# RELAY.net
KiCad netlist of a schematic drawn in Altium Designer
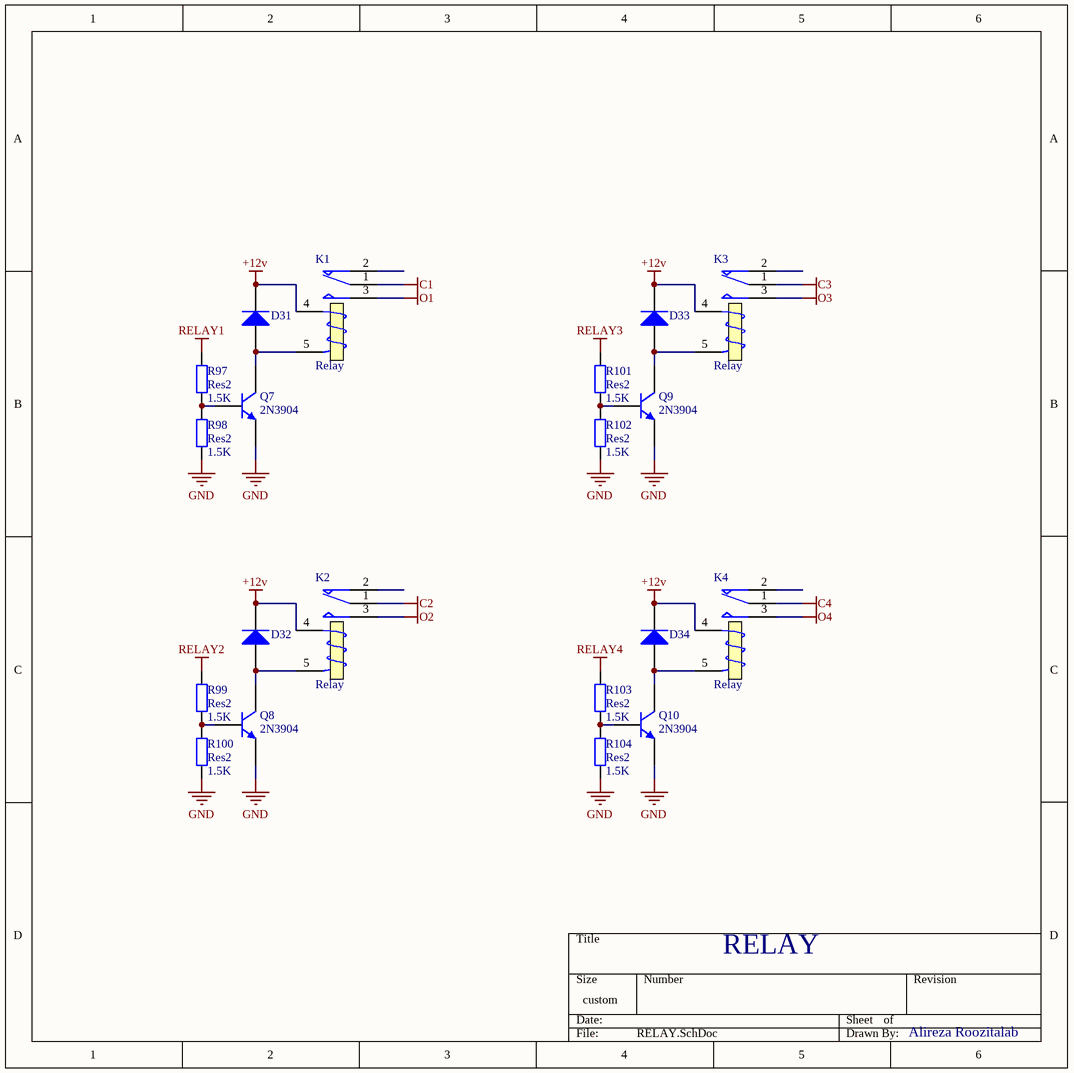
[diagram p0: RELAY.SchDoc]

(export (version "E")
  (design (tool "Eeschema 10.0.6"))
  (components
    (comp (ref "D31")
      (value "Diode 1N4148")
      (footprint "Diode-1n4148 - SMD PAD")
      (description "High Conductance Fast Diode")
      (fields (field (name "PUBLISHER") "Altium Limited"))
      (libsource (lib "Miscellaneous Devices") (part "Diode 1N4148"))
    )
    (comp (ref "D32")
      (value "Diode 1N4148")
      (footprint "Diode-1n4148 - SMD PAD")
      (description "High Conductance Fast Diode")
      (fields (field (name "PUBLISHER") "Altium Limited"))
      (libsource (lib "Miscellaneous Devices") (part "Diode 1N4148"))
    )
    (comp (ref "D33")
      (value "Diode 1N4148")
      (footprint "Diode-1n4148 - SMD PAD")
      (description "High Conductance Fast Diode")
      (fields (field (name "PUBLISHER") "Altium Limited"))
      (libsource (lib "Miscellaneous Devices") (part "Diode 1N4148"))
    )
    (comp (ref "D34")
      (value "Diode 1N4148")
      (footprint "Diode-1n4148 - SMD PAD")
      (description "High Conductance Fast Diode")
      (fields (field (name "PUBLISHER") "Altium Limited"))
      (libsource (lib "Miscellaneous Devices") (part "Diode 1N4148"))
    )
    (comp (ref "K1")
      (value "Relay")
      (footprint "RELAY 12V ATX203")
      (description "SPDT Relay")
      (fields (field (name "PUBLISHER") "Altium Limited"))
      (libsource (lib "Miscellaneous Devices") (part "Relay"))
    )
    (comp (ref "K2")
      (value "Relay")
      (footprint "RELAY 12V ATX203")
      (description "SPDT Relay")
      (fields (field (name "PUBLISHER") "Altium Limited"))
      (libsource (lib "Miscellaneous Devices") (part "Relay"))
    )
    (comp (ref "K3")
      (value "Relay")
      (footprint "RELAY 12V ATX203")
      (description "SPDT Relay")
      (fields (field (name "PUBLISHER") "Altium Limited"))
      (libsource (lib "Miscellaneous Devices") (part "Relay"))
    )
    (comp (ref "K4")
      (value "Relay")
      (footprint "RELAY 12V ATX203")
      (description "SPDT Relay")
      (fields (field (name "PUBLISHER") "Altium Limited"))
      (libsource (lib "Miscellaneous Devices") (part "Relay"))
    )
    (comp (ref "Q7")
      (value "2N3904")
      (footprint "2N3906_SMD")
      (description "NPN General Purpose Amplifier")
      (fields (field (name "PUBLISHER") "Altium Limited"))
      (libsource (lib "Miscellaneous Devices") (part "2N3904"))
    )
    (comp (ref "Q8")
      (value "2N3904")
      (footprint "2N3906_SMD")
      (description "NPN General Purpose Amplifier")
      (fields (field (name "PUBLISHER") "Altium Limited"))
      (libsource (lib "Miscellaneous Devices") (part "2N3904"))
    )
    (comp (ref "Q9")
      (value "2N3904")
      (footprint "2N3906_SMD")
      (description "NPN General Purpose Amplifier")
      (fields (field (name "PUBLISHER") "Altium Limited"))
      (libsource (lib "Miscellaneous Devices") (part "2N3904"))
    )
    (comp (ref "Q10")
      (value "2N3904")
      (footprint "2N3906_SMD")
      (description "NPN General Purpose Amplifier")
      (fields (field (name "PUBLISHER") "Altium Limited"))
      (libsource (lib "Miscellaneous Devices") (part "2N3904"))
    )
    (comp (ref "R97")
      (value "Res2")
      (footprint "RES 1206 (3216X08L)")
      (description "Resistor")
      (fields (field (name "ALTIUM_VALUE") "1.5K") (field (name "PUBLISHER") "Altium Limited"))
      (libsource (lib "Miscellaneous Devices") (part "Res2"))
    )
    (comp (ref "R98")
      (value "Res2")
      (footprint "RES 1206 (3216X08L)")
      (description "Resistor")
      (fields (field (name "ALTIUM_VALUE") "1.5K") (field (name "PUBLISHER") "Altium Limited"))
      (libsource (lib "Miscellaneous Devices") (part "Res2"))
    )
    (comp (ref "R99")
      (value "Res2")
      (footprint "RES 1206 (3216X08L)")
      (description "Resistor")
      (fields (field (name "ALTIUM_VALUE") "1.5K") (field (name "PUBLISHER") "Altium Limited"))
      (libsource (lib "Miscellaneous Devices") (part "Res2"))
    )
    (comp (ref "R100")
      (value "Res2")
      (footprint "RES 1206 (3216X08L)")
      (description "Resistor")
      (fields (field (name "ALTIUM_VALUE") "1.5K") (field (name "PUBLISHER") "Altium Limited"))
      (libsource (lib "Miscellaneous Devices") (part "Res2"))
    )
    (comp (ref "R101")
      (value "Res2")
      (footprint "RES 1206 (3216X08L)")
      (description "Resistor")
      (fields (field (name "ALTIUM_VALUE") "1.5K") (field (name "PUBLISHER") "Altium Limited"))
      (libsource (lib "Miscellaneous Devices") (part "Res2"))
    )
    (comp (ref "R102")
      (value "Res2")
      (footprint "RES 1206 (3216X08L)")
      (description "Resistor")
      (fields (field (name "ALTIUM_VALUE") "1.5K") (field (name "PUBLISHER") "Altium Limited"))
      (libsource (lib "Miscellaneous Devices") (part "Res2"))
    )
    (comp (ref "R103")
      (value "Res2")
      (footprint "RES 1206 (3216X08L)")
      (description "Resistor")
      (fields (field (name "ALTIUM_VALUE") "1.5K") (field (name "PUBLISHER") "Altium Limited"))
      (libsource (lib "Miscellaneous Devices") (part "Res2"))
    )
    (comp (ref "R104")
      (value "Res2")
      (footprint "RES 1206 (3216X08L)")
      (description "Resistor")
      (fields (field (name "ALTIUM_VALUE") "1.5K") (field (name "PUBLISHER") "Altium Limited"))
      (libsource (lib "Miscellaneous Devices") (part "Res2"))
    )
  )
  (nets
    (net (code "1") (name "+12v") (class "Default")
      (node (ref "D31") (pin "2") (pinfunction "K_2") (pintype "passive"))
      (node (ref "D32") (pin "2") (pinfunction "K_2") (pintype "passive"))
      (node (ref "D33") (pin "2") (pinfunction "K_2") (pintype "passive"))
      (node (ref "D34") (pin "2") (pinfunction "K_2") (pintype "passive"))
      (node (ref "K1") (pin "4") (pinfunction "4_4") (pintype "passive"))
      (node (ref "K2") (pin "4") (pinfunction "4_4") (pintype "passive"))
      (node (ref "K3") (pin "4") (pinfunction "4_4") (pintype "passive"))
      (node (ref "K4") (pin "4") (pinfunction "4_4") (pintype "passive"))
    )
    (net (code "2") (name "C1") (class "Default")
      (node (ref "K1") (pin "1") (pinfunction "1_1") (pintype "passive"))
    )
    (net (code "3") (name "C2") (class "Default")
      (node (ref "K2") (pin "1") (pinfunction "1_1") (pintype "passive"))
    )
    (net (code "4") (name "C3") (class "Default")
      (node (ref "K3") (pin "1") (pinfunction "1_1") (pintype "passive"))
    )
    (net (code "5") (name "C4") (class "Default")
      (node (ref "K4") (pin "1") (pinfunction "1_1") (pintype "passive"))
    )
    (net (code "6") (name "GND") (class "Default")
      (node (ref "Q10") (pin "1") (pinfunction "E_1") (pintype "passive"))
      (node (ref "Q7") (pin "1") (pinfunction "E_1") (pintype "passive"))
      (node (ref "Q8") (pin "1") (pinfunction "E_1") (pintype "passive"))
      (node (ref "Q9") (pin "1") (pinfunction "E_1") (pintype "passive"))
      (node (ref "R100") (pin "1") (pinfunction "1_1") (pintype "passive"))
      (node (ref "R102") (pin "1") (pinfunction "1_1") (pintype "passive"))
      (node (ref "R104") (pin "1") (pinfunction "1_1") (pintype "passive"))
      (node (ref "R98") (pin "1") (pinfunction "1_1") (pintype "passive"))
    )
    (net (code "7") (name "Net-(D31-A)") (class "Default")
      (node (ref "D31") (pin "1") (pinfunction "A_1") (pintype "passive"))
      (node (ref "K1") (pin "5") (pinfunction "5_5") (pintype "passive"))
      (node (ref "Q7") (pin "3") (pinfunction "C_3") (pintype "passive"))
    )
    (net (code "8") (name "Net-(D32-A)") (class "Default")
      (node (ref "D32") (pin "1") (pinfunction "A_1") (pintype "passive"))
      (node (ref "K2") (pin "5") (pinfunction "5_5") (pintype "passive"))
      (node (ref "Q8") (pin "3") (pinfunction "C_3") (pintype "passive"))
    )
    (net (code "9") (name "Net-(D33-A)") (class "Default")
      (node (ref "D33") (pin "1") (pinfunction "A_1") (pintype "passive"))
      (node (ref "K3") (pin "5") (pinfunction "5_5") (pintype "passive"))
      (node (ref "Q9") (pin "3") (pinfunction "C_3") (pintype "passive"))
    )
    (net (code "10") (name "Net-(D34-A)") (class "Default")
      (node (ref "D34") (pin "1") (pinfunction "A_1") (pintype "passive"))
      (node (ref "K4") (pin "5") (pinfunction "5_5") (pintype "passive"))
      (node (ref "Q10") (pin "3") (pinfunction "C_3") (pintype "passive"))
    )
    (net (code "11") (name "Net-(Q7-B)") (class "Default")
      (node (ref "Q7") (pin "2") (pinfunction "B_2") (pintype "passive"))
      (node (ref "R97") (pin "1") (pinfunction "1_1") (pintype "passive"))
      (node (ref "R98") (pin "2") (pinfunction "2_2") (pintype "passive"))
    )
    (net (code "12") (name "Net-(Q8-B)") (class "Default")
      (node (ref "Q8") (pin "2") (pinfunction "B_2") (pintype "passive"))
      (node (ref "R100") (pin "2") (pinfunction "2_2") (pintype "passive"))
      (node (ref "R99") (pin "1") (pinfunction "1_1") (pintype "passive"))
    )
    (net (code "13") (name "Net-(Q9-B)") (class "Default")
      (node (ref "Q9") (pin "2") (pinfunction "B_2") (pintype "passive"))
      (node (ref "R101") (pin "1") (pinfunction "1_1") (pintype "passive"))
      (node (ref "R102") (pin "2") (pinfunction "2_2") (pintype "passive"))
    )
    (net (code "14") (name "Net-(Q10-B)") (class "Default")
      (node (ref "Q10") (pin "2") (pinfunction "B_2") (pintype "passive"))
      (node (ref "R103") (pin "1") (pinfunction "1_1") (pintype "passive"))
      (node (ref "R104") (pin "2") (pinfunction "2_2") (pintype "passive"))
    )
    (net (code "15") (name "O1") (class "Default")
      (node (ref "K1") (pin "3") (pinfunction "3_3") (pintype "passive"))
    )
    (net (code "16") (name "O2") (class "Default")
      (node (ref "K2") (pin "3") (pinfunction "3_3") (pintype "passive"))
    )
    (net (code "17") (name "O3") (class "Default")
      (node (ref "K3") (pin "3") (pinfunction "3_3") (pintype "passive"))
    )
    (net (code "18") (name "O4") (class "Default")
      (node (ref "K4") (pin "3") (pinfunction "3_3") (pintype "passive"))
    )
    (net (code "19") (name "RELAY1") (class "Default")
      (node (ref "R97") (pin "2") (pinfunction "2_2") (pintype "passive"))
    )
    (net (code "20") (name "RELAY2") (class "Default")
      (node (ref "R99") (pin "2") (pinfunction "2_2") (pintype "passive"))
    )
    (net (code "21") (name "RELAY3") (class "Default")
      (node (ref "R101") (pin "2") (pinfunction "2_2") (pintype "passive"))
    )
    (net (code "22") (name "RELAY4") (class "Default")
      (node (ref "R103") (pin "2") (pinfunction "2_2") (pintype "passive"))
    )
    (net (code "23") (name "unconnected-(K1-Pad2)") (class "Default")
      (node (ref "K1") (pin "2") (pinfunction "2_2") (pintype "passive"))
    )
    (net (code "24") (name "unconnected-(K2-Pad2)") (class "Default")
      (node (ref "K2") (pin "2") (pinfunction "2_2") (pintype "passive"))
    )
    (net (code "25") (name "unconnected-(K3-Pad2)") (class "Default")
      (node (ref "K3") (pin "2") (pinfunction "2_2") (pintype "passive"))
    )
    (net (code "26") (name "unconnected-(K4-Pad2)") (class "Default")
      (node (ref "K4") (pin "2") (pinfunction "2_2") (pintype "passive"))
    )
  )
)
